# encoder.net
KiCad netlist of a schematic drawn in EasyEDA Pro
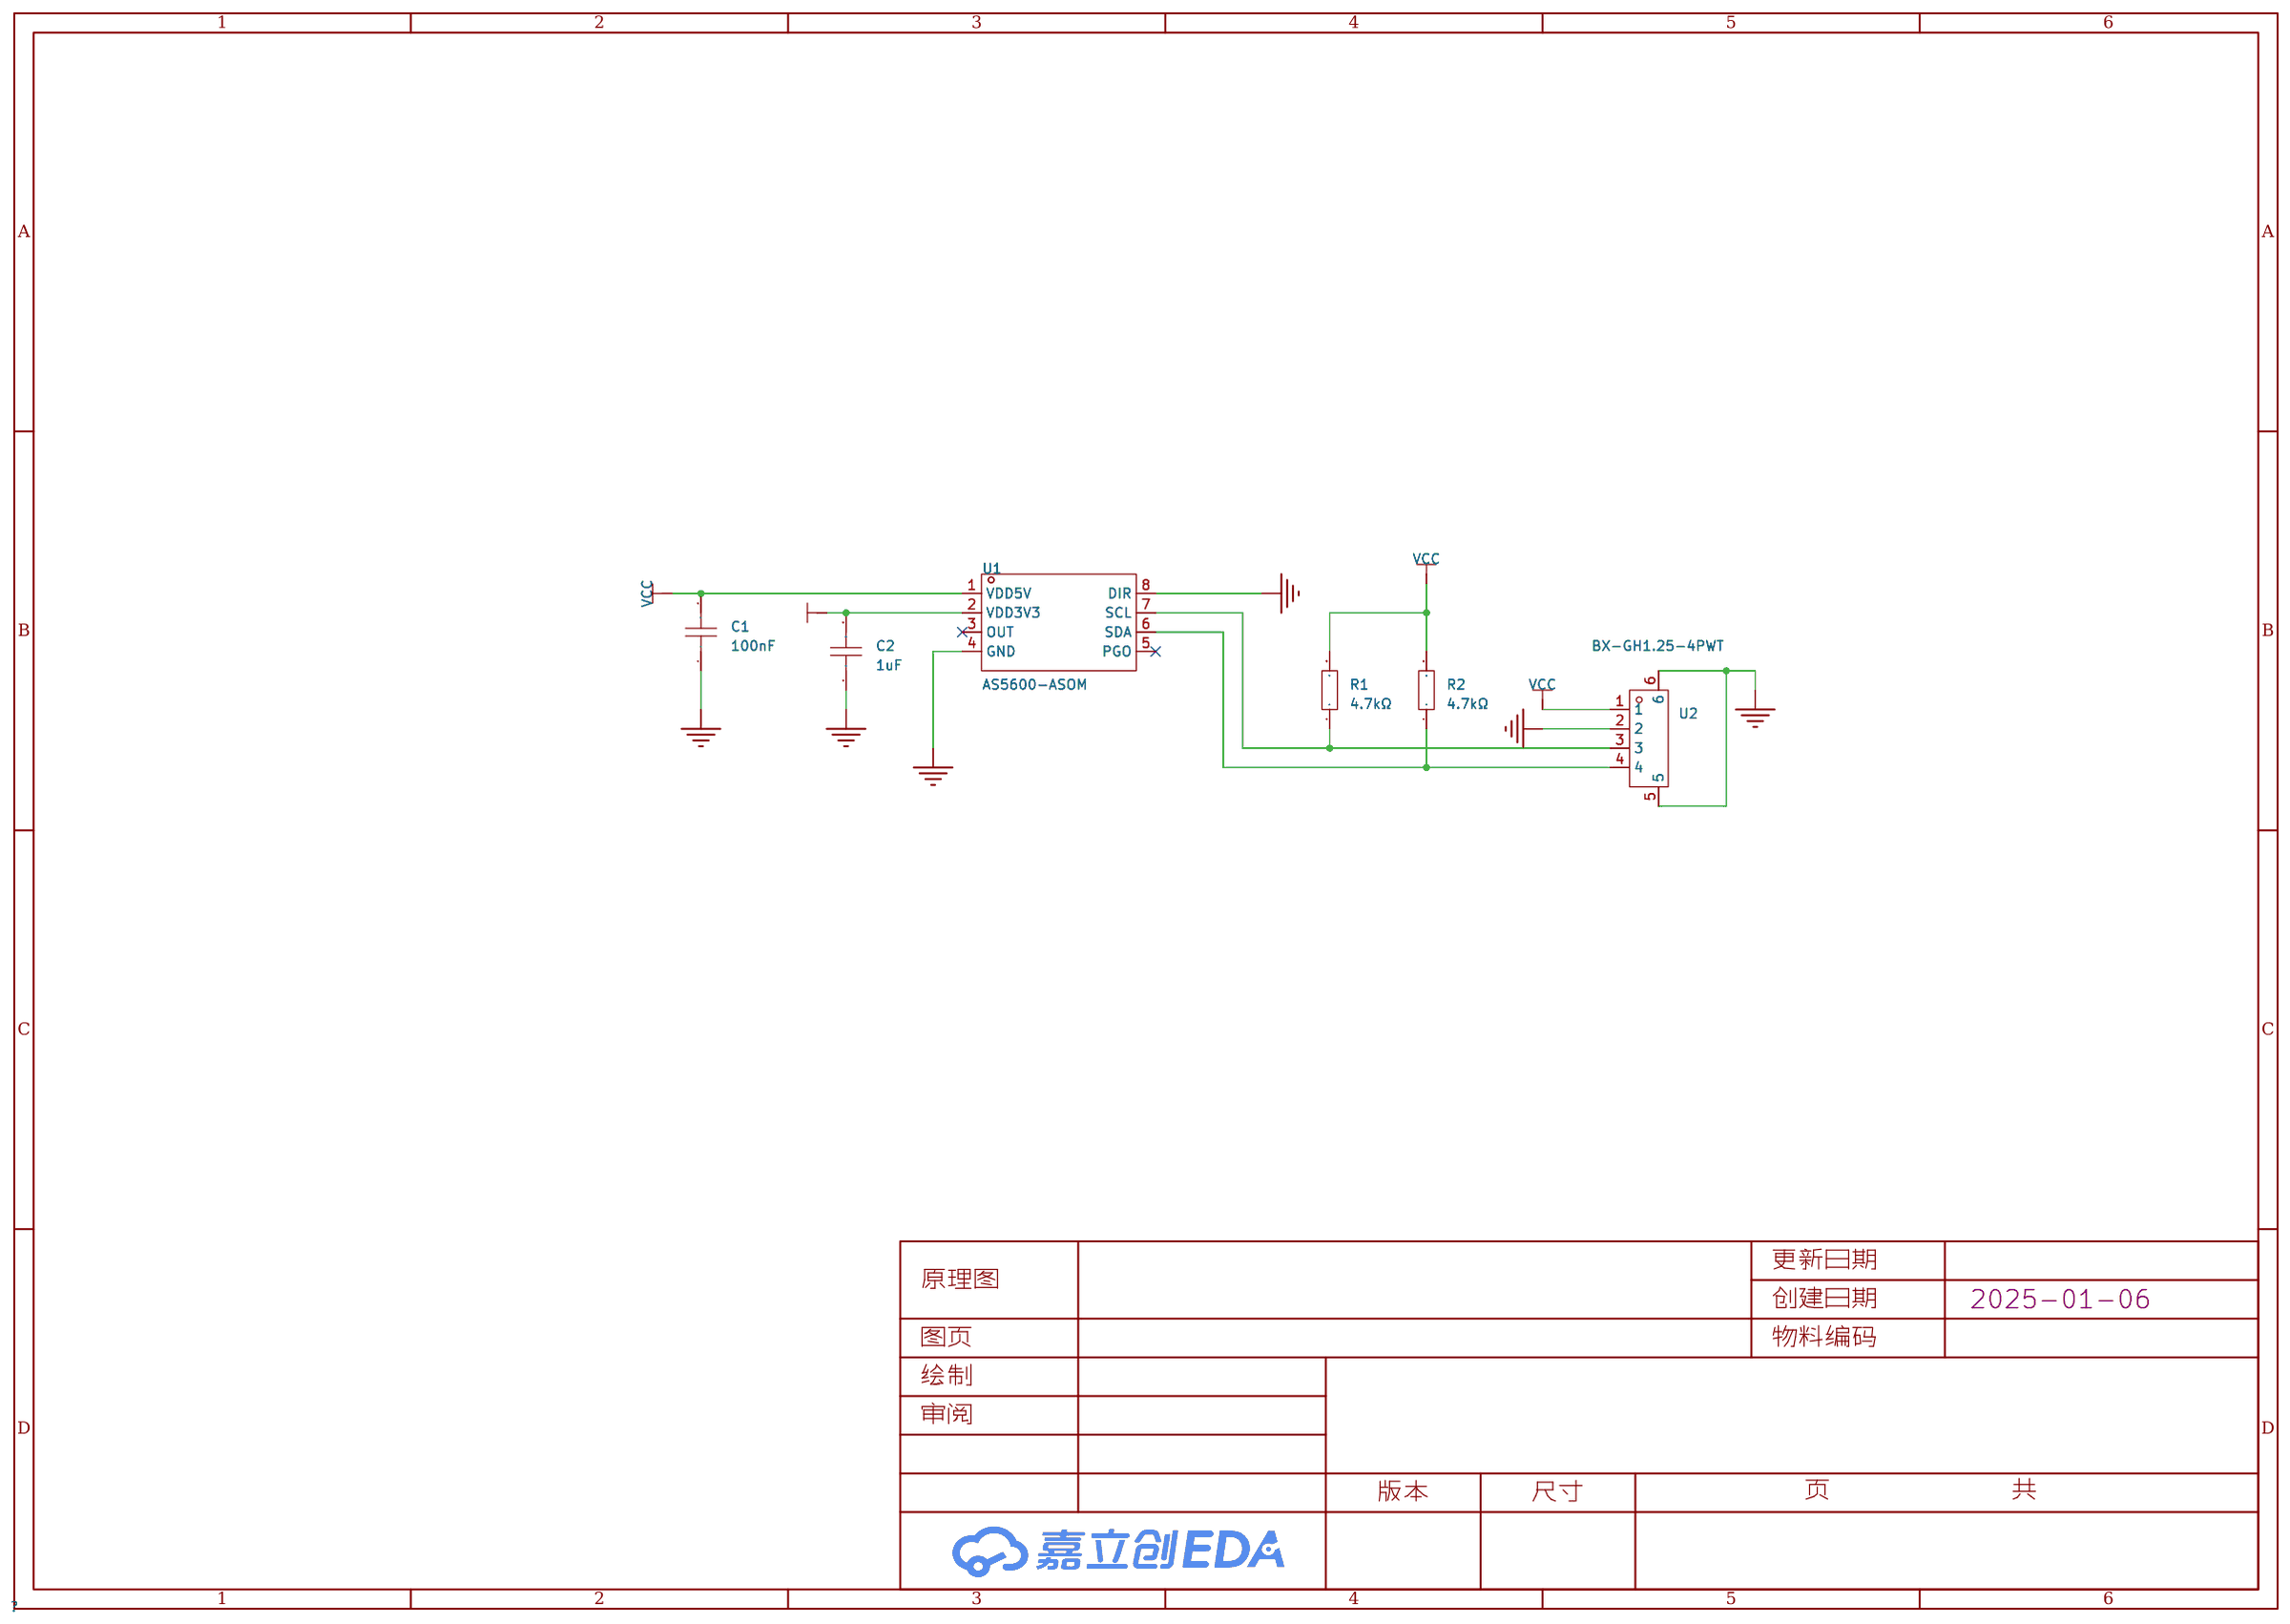
[diagram p0: schematic sheet]

(export (version "E")
  (design (tool "Eeschema 10.0.6"))
  (components
    (comp (ref "C1")
      (value "100nF")
      (footprint "easyedapro:C0603")
      (description "容值:100nF;精度:±10%;额定电压:50V;材质(温度系数):X7R;")
      (fields
        (field (name "Manufacturer Part") "CGA0603X7R104K500JT")
        (field (name "Manufacturer") "HRE(芯声)")
      )
      (libsource (lib "easyedapro") (part "CGA0603X7R104K500JT"))
    )
    (comp (ref "C2")
      (value "1uF")
      (footprint "easyedapro:C0603")
      (description "容值:100nF;精度:±10%;额定电压:50V;材质(温度系数):X7R;")
      (fields
        (field (name "Manufacturer Part") "CGA0603X7R104K500JT")
        (field (name "Manufacturer") "HRE(芯声)")
      )
      (libsource (lib "easyedapro") (part "CGA0603X7R104K500JT"))
    )
    (comp (ref "R1")
      (value "4.7kΩ")
      (footprint "easyedapro:R0603")
      (description "电阻类型:厚膜电阻;阻值:4.7kΩ;精度:±1%;功率:100mW;最大工作电压:75V;温度系数:±100ppm/°C;")
      (fields
        (field (name "Manufacturer Part") "0603WAF4701T5E")
        (field (name "Manufacturer") "UNI-ROYAL(厚声)")
      )
      (libsource (lib "easyedapro") (part "0603WAF4701T5E"))
    )
    (comp (ref "R2")
      (value "4.7kΩ")
      (footprint "easyedapro:R0603")
      (description "电阻类型:厚膜电阻;阻值:4.7kΩ;精度:±1%;功率:100mW;最大工作电压:75V;温度系数:±100ppm/°C;")
      (fields
        (field (name "Manufacturer Part") "0603WAF4701T5E")
        (field (name "Manufacturer") "UNI-ROYAL(厚声)")
      )
      (libsource (lib "easyedapro") (part "0603WAF4701T5E"))
    )
    (comp (ref "U1")
      (value "AS5600-ASOM")
      (footprint "easyedapro:SOIC-8_L5.0-W4.0-P1.27-LS6.0-BL")
      (description "旋转角度范围:0°~360°;")
      (fields (field (name "Manufacturer") "ams(艾迈斯半导体)"))
      (libsource (lib "easyedapro") (part "AS5600-ASOM"))
    )
    (comp (ref "U2")
      (value "BX-GH1.25-4PWT")
      (footprint "easyedapro:CONN-SMD_4P-P1.25_BX-GH1.25-4PWT")
      (fields (field (name "Manufacturer") "Bossie(博锡)"))
      (libsource (lib "easyedapro") (part "BX-GH1.25-4PWT"))
    )
  )
  (nets
    (net (code "1") (name "GND") (class "Default")
      (node (ref "C1") (pin "1") (pinfunction "1_1") (pintype "unspecified"))
      (node (ref "C2") (pin "1") (pinfunction "1_1") (pintype "unspecified"))
      (node (ref "U1") (pin "4") (pinfunction "GND_4") (pintype "unspecified"))
      (node (ref "U1") (pin "8") (pinfunction "DIR_8") (pintype "unspecified"))
      (node (ref "U2") (pin "2") (pinfunction "2_2") (pintype "unspecified"))
      (node (ref "U2") (pin "5") (pinfunction "5_5") (pintype "unspecified"))
      (node (ref "U2") (pin "6") (pinfunction "6_6") (pintype "unspecified"))
    )
    (net (code "2") (name "Net-(U1-SCL)") (class "Default")
      (node (ref "R1") (pin "1") (pinfunction "1_1") (pintype "input"))
      (node (ref "U1") (pin "7") (pinfunction "SCL_7") (pintype "unspecified"))
      (node (ref "U2") (pin "3") (pinfunction "3_3") (pintype "unspecified"))
    )
    (net (code "3") (name "Net-(U1-SDA)") (class "Default")
      (node (ref "R2") (pin "1") (pinfunction "1_1") (pintype "input"))
      (node (ref "U1") (pin "6") (pinfunction "SDA_6") (pintype "unspecified"))
      (node (ref "U2") (pin "4") (pinfunction "4_4") (pintype "unspecified"))
    )
    (net (code "4") (name "VCC") (class "Default")
      (node (ref "C1") (pin "2") (pinfunction "2_2") (pintype "unspecified"))
      (node (ref "R1") (pin "2") (pinfunction "2_2") (pintype "input"))
      (node (ref "R2") (pin "2") (pinfunction "2_2") (pintype "input"))
      (node (ref "U1") (pin "1") (pinfunction "VDD5V_1") (pintype "unspecified"))
      (node (ref "U2") (pin "1") (pinfunction "1_1") (pintype "unspecified"))
    )
    (net (code "5") (name "VCC3.3") (class "Default")
      (node (ref "C2") (pin "2") (pinfunction "2_2") (pintype "unspecified"))
      (node (ref "U1") (pin "2") (pinfunction "VDD3V3_2") (pintype "unspecified"))
    )
    (net (code "6") (name "unconnected-(U1-OUT-Pad3)") (class "Default")
      (node (ref "U1") (pin "3") (pinfunction "OUT_3") (pintype "unspecified+no_connect"))
    )
    (net (code "7") (name "unconnected-(U1-PGO-Pad5)") (class "Default")
      (node (ref "U1") (pin "5") (pinfunction "PGO_5") (pintype "unspecified+no_connect"))
    )
  )
)
